# mk3-schield.net
KiCad netlist of a schematic drawn in EAGLE
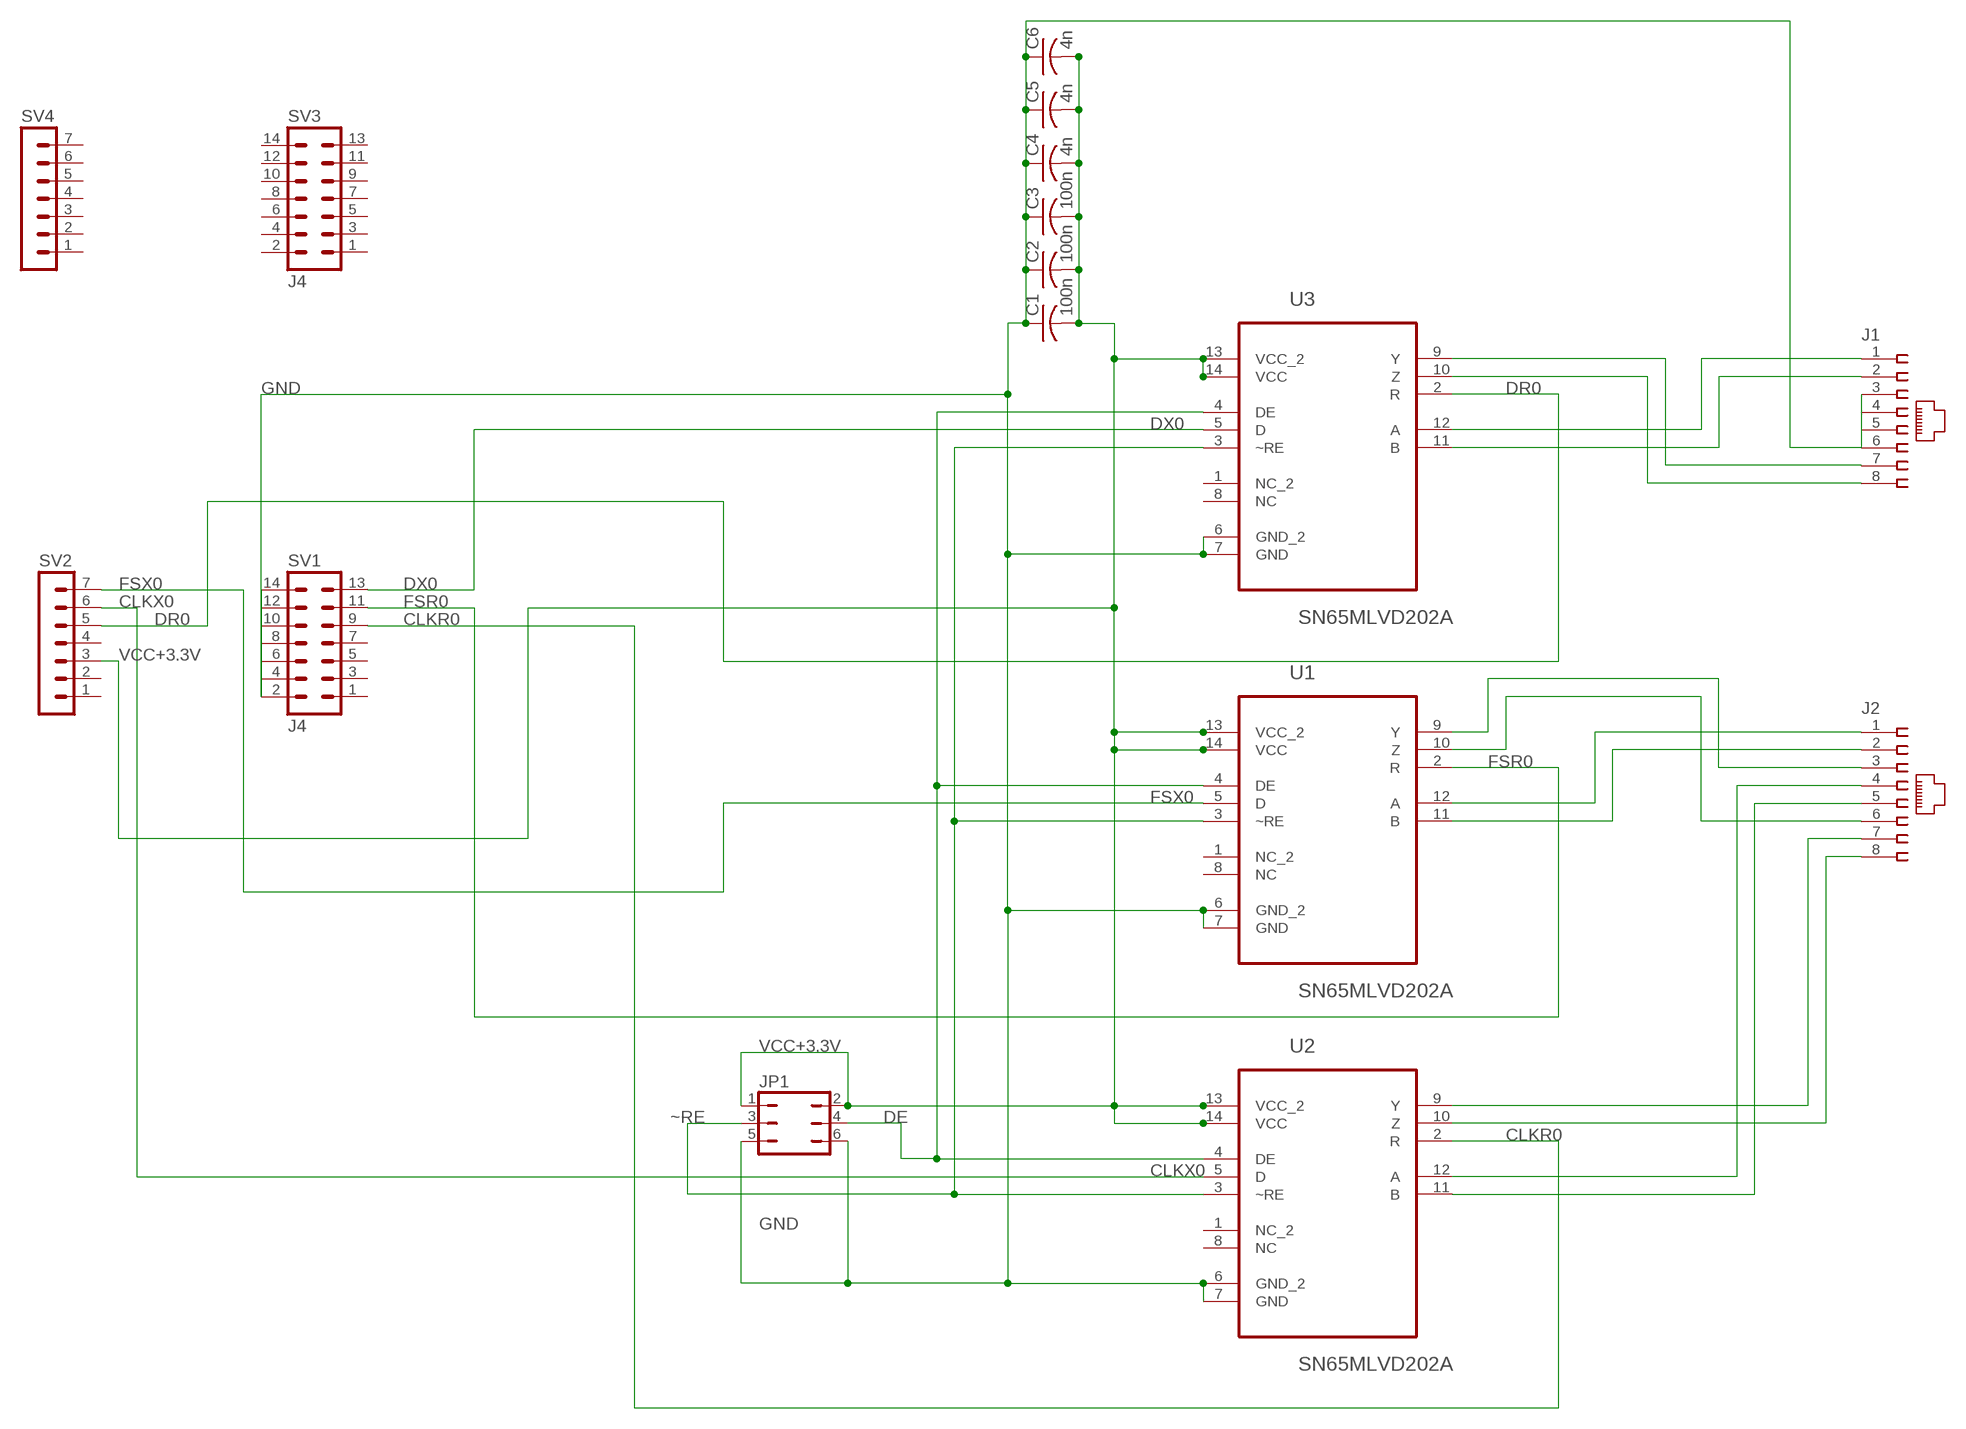
[diagram p0: schematic, sheet 1]

(export (version "E")
  (design (tool "Eeschema 10.0.6"))
  (components
    (comp (ref "C1")
      (value "100n")
      (footprint "eagle-import:C0805")
      (libsource (lib "eagle-import") (part "C-USC0805"))
    )
    (comp (ref "C2")
      (value "100n")
      (footprint "eagle-import:C0805")
      (libsource (lib "eagle-import") (part "C-USC0805"))
    )
    (comp (ref "C3")
      (value "100n")
      (footprint "eagle-import:C0805")
      (libsource (lib "eagle-import") (part "C-USC0805"))
    )
    (comp (ref "C4")
      (value "4n")
      (footprint "eagle-import:C0805")
      (libsource (lib "eagle-import") (part "C-USC0805"))
    )
    (comp (ref "C5")
      (value "4n")
      (footprint "eagle-import:C0805")
      (libsource (lib "eagle-import") (part "C-USC0805"))
    )
    (comp (ref "C6")
      (value "4n")
      (footprint "eagle-import:C0805")
      (libsource (lib "eagle-import") (part "C-USC0805"))
    )
    (comp (ref "J1")
      (value "557785-1-SHIELD")
      (footprint "eagle-import:557785-1")
      (libsource (lib "eagle-import") (part "557785-1-SHIELD"))
    )
    (comp (ref "J2")
      (value "557785-1-SHIELD")
      (footprint "eagle-import:557785-1")
      (libsource (lib "eagle-import") (part "557785-1-SHIELD"))
    )
    (comp (ref "JP1")
      (value "JP3Q")
      (footprint "eagle-import:JP3Q")
      (libsource (lib "eagle-import") (part "JP3Q"))
    )
    (comp (ref "SV1")
      (value "J4")
      (footprint "eagle-import:MA07-2")
      (libsource (lib "eagle-import") (part "MA07-2"))
    )
    (comp (ref "SV2")
      (value "MA07-1")
      (footprint "eagle-import:MA07-1")
      (libsource (lib "eagle-import") (part "MA07-1"))
    )
    (comp (ref "SV3")
      (value "J4")
      (footprint "eagle-import:MA07-2")
      (libsource (lib "eagle-import") (part "MA07-2"))
    )
    (comp (ref "SV4")
      (value "MA07-1")
      (footprint "eagle-import:MA07-1")
      (libsource (lib "eagle-import") (part "MA07-1"))
    )
    (comp (ref "U1")
      (value "SN65MLVD202A")
      (footprint "eagle-import:SOIC127P600X175-14N")
      (fields (field (name "MPN") "SN65MLVD205AD"))
      (libsource (lib "eagle-import") (part "SN65MLVD205AD"))
    )
    (comp (ref "U2")
      (value "SN65MLVD202A")
      (footprint "eagle-import:SOIC127P600X175-14N")
      (fields (field (name "MPN") "SN65MLVD205AD"))
      (libsource (lib "eagle-import") (part "SN65MLVD205AD"))
    )
    (comp (ref "U3")
      (value "SN65MLVD202A")
      (footprint "eagle-import:SOIC127P600X175-14N")
      (fields (field (name "MPN") "SN65MLVD205AD"))
      (libsource (lib "eagle-import") (part "SN65MLVD205AD"))
    )
  )
  (nets
    (net (code "1") (name "/CLKR0") (class "Default")
      (node (ref "SV1") (pin "9") (pinfunction "9_9") (pintype "passive"))
      (node (ref "U2") (pin "2") (pinfunction "R_2") (pintype "output"))
    )
    (net (code "2") (name "/CLKX0") (class "Default")
      (node (ref "SV2") (pin "6") (pinfunction "6_6") (pintype "passive"))
      (node (ref "U2") (pin "5") (pinfunction "D_5") (pintype "input"))
    )
    (net (code "3") (name "/DE") (class "Default")
      (node (ref "JP1") (pin "4") (pinfunction "4_4") (pintype "passive"))
      (node (ref "U1") (pin "4") (pinfunction "DE_4") (pintype "input"))
      (node (ref "U2") (pin "4") (pinfunction "DE_4") (pintype "input"))
      (node (ref "U3") (pin "4") (pinfunction "DE_4") (pintype "input"))
    )
    (net (code "4") (name "/DR0") (class "Default")
      (node (ref "SV2") (pin "5") (pinfunction "5_5") (pintype "passive"))
      (node (ref "U3") (pin "2") (pinfunction "R_2") (pintype "output"))
    )
    (net (code "5") (name "/DX0") (class "Default")
      (node (ref "SV1") (pin "13") (pinfunction "13_13") (pintype "passive"))
      (node (ref "U3") (pin "5") (pinfunction "D_5") (pintype "input"))
    )
    (net (code "6") (name "/FSR0") (class "Default")
      (node (ref "SV1") (pin "11") (pinfunction "11_11") (pintype "passive"))
      (node (ref "U1") (pin "2") (pinfunction "R_2") (pintype "output"))
    )
    (net (code "7") (name "/FSX0") (class "Default")
      (node (ref "SV2") (pin "7") (pinfunction "7_7") (pintype "passive"))
      (node (ref "U1") (pin "5") (pinfunction "D_5") (pintype "input"))
    )
    (net (code "8") (name "/GND") (class "Default")
      (node (ref "C1") (pin "1") (pinfunction "1_1") (pintype "passive"))
      (node (ref "C2") (pin "1") (pinfunction "1_1") (pintype "passive"))
      (node (ref "C3") (pin "1") (pinfunction "1_1") (pintype "passive"))
      (node (ref "C4") (pin "1") (pinfunction "1_1") (pintype "passive"))
      (node (ref "C5") (pin "1") (pinfunction "1_1") (pintype "passive"))
      (node (ref "C6") (pin "1") (pinfunction "1_1") (pintype "passive"))
      (node (ref "J1") (pin "3") (pinfunction "3_3") (pintype "passive"))
      (node (ref "J1") (pin "4") (pinfunction "4_4") (pintype "passive"))
      (node (ref "J1") (pin "5") (pinfunction "5_5") (pintype "passive"))
      (node (ref "J1") (pin "6") (pinfunction "6_6") (pintype "passive"))
      (node (ref "JP1") (pin "5") (pinfunction "5_5") (pintype "passive"))
      (node (ref "JP1") (pin "6") (pinfunction "6_6") (pintype "passive"))
      (node (ref "SV1") (pin "10") (pinfunction "10_10") (pintype "passive"))
      (node (ref "SV1") (pin "12") (pinfunction "12_12") (pintype "passive"))
      (node (ref "SV1") (pin "14") (pinfunction "14_14") (pintype "passive"))
      (node (ref "SV1") (pin "2") (pinfunction "2_2") (pintype "passive"))
      (node (ref "SV1") (pin "4") (pinfunction "4_4") (pintype "passive"))
      (node (ref "SV1") (pin "6") (pinfunction "6_6") (pintype "passive"))
      (node (ref "SV1") (pin "8") (pinfunction "8_8") (pintype "passive"))
      (node (ref "U1") (pin "6") (pinfunction "GND_2_6") (pintype "passive"))
      (node (ref "U1") (pin "7") (pinfunction "GND_7") (pintype "passive"))
      (node (ref "U2") (pin "6") (pinfunction "GND_2_6") (pintype "passive"))
      (node (ref "U2") (pin "7") (pinfunction "GND_7") (pintype "passive"))
      (node (ref "U3") (pin "6") (pinfunction "GND_2_6") (pintype "passive"))
      (node (ref "U3") (pin "7") (pinfunction "GND_7") (pintype "passive"))
    )
    (net (code "9") (name "/VCC+3.3V") (class "Default")
      (node (ref "C1") (pin "2") (pinfunction "2_2") (pintype "passive"))
      (node (ref "C2") (pin "2") (pinfunction "2_2") (pintype "passive"))
      (node (ref "C3") (pin "2") (pinfunction "2_2") (pintype "passive"))
      (node (ref "C4") (pin "2") (pinfunction "2_2") (pintype "passive"))
      (node (ref "C5") (pin "2") (pinfunction "2_2") (pintype "passive"))
      (node (ref "C6") (pin "2") (pinfunction "2_2") (pintype "passive"))
      (node (ref "JP1") (pin "1") (pinfunction "1_1") (pintype "passive"))
      (node (ref "JP1") (pin "2") (pinfunction "2_2") (pintype "passive"))
      (node (ref "SV2") (pin "3") (pinfunction "3_3") (pintype "passive"))
      (node (ref "U1") (pin "13") (pinfunction "VCC_2_13") (pintype "power_in"))
      (node (ref "U1") (pin "14") (pinfunction "VCC_14") (pintype "power_in"))
      (node (ref "U2") (pin "13") (pinfunction "VCC_2_13") (pintype "power_in"))
      (node (ref "U2") (pin "14") (pinfunction "VCC_14") (pintype "power_in"))
      (node (ref "U3") (pin "13") (pinfunction "VCC_2_13") (pintype "power_in"))
      (node (ref "U3") (pin "14") (pinfunction "VCC_14") (pintype "power_in"))
    )
    (net (code "10") (name "/~{RE}") (class "Default")
      (node (ref "JP1") (pin "3") (pinfunction "3_3") (pintype "passive"))
      (node (ref "U1") (pin "3") (pinfunction "~{RE}_3") (pintype "input"))
      (node (ref "U2") (pin "3") (pinfunction "~{RE}_3") (pintype "input"))
      (node (ref "U3") (pin "3") (pinfunction "~{RE}_3") (pintype "input"))
    )
    (net (code "11") (name "Net-(U1-A)") (class "Default")
      (node (ref "J2") (pin "1") (pinfunction "1_1") (pintype "passive"))
      (node (ref "U1") (pin "12") (pinfunction "A_12") (pintype "output"))
    )
    (net (code "12") (name "Net-(U1-B)") (class "Default")
      (node (ref "J2") (pin "2") (pinfunction "2_2") (pintype "passive"))
      (node (ref "U1") (pin "11") (pinfunction "B_11") (pintype "output"))
    )
    (net (code "13") (name "Net-(U1-Y)") (class "Default")
      (node (ref "J2") (pin "3") (pinfunction "3_3") (pintype "passive"))
      (node (ref "U1") (pin "9") (pinfunction "Y_9") (pintype "output"))
    )
    (net (code "14") (name "Net-(U1-Z)") (class "Default")
      (node (ref "J2") (pin "6") (pinfunction "6_6") (pintype "passive"))
      (node (ref "U1") (pin "10") (pinfunction "Z_10") (pintype "output"))
    )
    (net (code "15") (name "Net-(U2-A)") (class "Default")
      (node (ref "J2") (pin "4") (pinfunction "4_4") (pintype "passive"))
      (node (ref "U2") (pin "12") (pinfunction "A_12") (pintype "output"))
    )
    (net (code "16") (name "Net-(U2-B)") (class "Default")
      (node (ref "J2") (pin "5") (pinfunction "5_5") (pintype "passive"))
      (node (ref "U2") (pin "11") (pinfunction "B_11") (pintype "output"))
    )
    (net (code "17") (name "Net-(U2-Y)") (class "Default")
      (node (ref "J2") (pin "7") (pinfunction "7_7") (pintype "passive"))
      (node (ref "U2") (pin "9") (pinfunction "Y_9") (pintype "output"))
    )
    (net (code "18") (name "Net-(U2-Z)") (class "Default")
      (node (ref "J2") (pin "8") (pinfunction "8_8") (pintype "passive"))
      (node (ref "U2") (pin "10") (pinfunction "Z_10") (pintype "output"))
    )
    (net (code "19") (name "Net-(U3-A)") (class "Default")
      (node (ref "J1") (pin "1") (pinfunction "1_1") (pintype "passive"))
      (node (ref "U3") (pin "12") (pinfunction "A_12") (pintype "output"))
    )
    (net (code "20") (name "Net-(U3-B)") (class "Default")
      (node (ref "J1") (pin "2") (pinfunction "2_2") (pintype "passive"))
      (node (ref "U3") (pin "11") (pinfunction "B_11") (pintype "output"))
    )
    (net (code "21") (name "Net-(U3-Y)") (class "Default")
      (node (ref "J1") (pin "7") (pinfunction "7_7") (pintype "passive"))
      (node (ref "U3") (pin "9") (pinfunction "Y_9") (pintype "output"))
    )
    (net (code "22") (name "Net-(U3-Z)") (class "Default")
      (node (ref "J1") (pin "8") (pinfunction "8_8") (pintype "passive"))
      (node (ref "U3") (pin "10") (pinfunction "Z_10") (pintype "output"))
    )
    (net (code "23") (name "unconnected-(SV1-Pad1)") (class "Default")
      (node (ref "SV1") (pin "1") (pinfunction "1_1") (pintype "passive"))
    )
    (net (code "24") (name "unconnected-(SV1-Pad3)") (class "Default")
      (node (ref "SV1") (pin "3") (pinfunction "3_3") (pintype "passive"))
    )
    (net (code "25") (name "unconnected-(SV1-Pad5)") (class "Default")
      (node (ref "SV1") (pin "5") (pinfunction "5_5") (pintype "passive"))
    )
    (net (code "26") (name "unconnected-(SV1-Pad7)") (class "Default")
      (node (ref "SV1") (pin "7") (pinfunction "7_7") (pintype "passive"))
    )
    (net (code "27") (name "unconnected-(SV2-Pad1)") (class "Default")
      (node (ref "SV2") (pin "1") (pinfunction "1_1") (pintype "passive"))
    )
    (net (code "28") (name "unconnected-(SV2-Pad2)") (class "Default")
      (node (ref "SV2") (pin "2") (pinfunction "2_2") (pintype "passive"))
    )
    (net (code "29") (name "unconnected-(SV2-Pad4)") (class "Default")
      (node (ref "SV2") (pin "4") (pinfunction "4_4") (pintype "passive"))
    )
    (net (code "30") (name "unconnected-(SV3-Pad1)") (class "Default")
      (node (ref "SV3") (pin "1") (pinfunction "1_1") (pintype "passive"))
    )
    (net (code "31") (name "unconnected-(SV3-Pad2)") (class "Default")
      (node (ref "SV3") (pin "2") (pinfunction "2_2") (pintype "passive"))
    )
    (net (code "32") (name "unconnected-(SV3-Pad3)") (class "Default")
      (node (ref "SV3") (pin "3") (pinfunction "3_3") (pintype "passive"))
    )
    (net (code "33") (name "unconnected-(SV3-Pad4)") (class "Default")
      (node (ref "SV3") (pin "4") (pinfunction "4_4") (pintype "passive"))
    )
    (net (code "34") (name "unconnected-(SV3-Pad5)") (class "Default")
      (node (ref "SV3") (pin "5") (pinfunction "5_5") (pintype "passive"))
    )
    (net (code "35") (name "unconnected-(SV3-Pad6)") (class "Default")
      (node (ref "SV3") (pin "6") (pinfunction "6_6") (pintype "passive"))
    )
    (net (code "36") (name "unconnected-(SV3-Pad7)") (class "Default")
      (node (ref "SV3") (pin "7") (pinfunction "7_7") (pintype "passive"))
    )
    (net (code "37") (name "unconnected-(SV3-Pad8)") (class "Default")
      (node (ref "SV3") (pin "8") (pinfunction "8_8") (pintype "passive"))
    )
    (net (code "38") (name "unconnected-(SV3-Pad9)") (class "Default")
      (node (ref "SV3") (pin "9") (pinfunction "9_9") (pintype "passive"))
    )
    (net (code "39") (name "unconnected-(SV3-Pad10)") (class "Default")
      (node (ref "SV3") (pin "10") (pinfunction "10_10") (pintype "passive"))
    )
    (net (code "40") (name "unconnected-(SV3-Pad11)") (class "Default")
      (node (ref "SV3") (pin "11") (pinfunction "11_11") (pintype "passive"))
    )
    (net (code "41") (name "unconnected-(SV3-Pad12)") (class "Default")
      (node (ref "SV3") (pin "12") (pinfunction "12_12") (pintype "passive"))
    )
    (net (code "42") (name "unconnected-(SV3-Pad13)") (class "Default")
      (node (ref "SV3") (pin "13") (pinfunction "13_13") (pintype "passive"))
    )
    (net (code "43") (name "unconnected-(SV3-Pad14)") (class "Default")
      (node (ref "SV3") (pin "14") (pinfunction "14_14") (pintype "passive"))
    )
    (net (code "44") (name "unconnected-(SV4-Pad1)") (class "Default")
      (node (ref "SV4") (pin "1") (pinfunction "1_1") (pintype "passive"))
    )
    (net (code "45") (name "unconnected-(SV4-Pad2)") (class "Default")
      (node (ref "SV4") (pin "2") (pinfunction "2_2") (pintype "passive"))
    )
    (net (code "46") (name "unconnected-(SV4-Pad3)") (class "Default")
      (node (ref "SV4") (pin "3") (pinfunction "3_3") (pintype "passive"))
    )
    (net (code "47") (name "unconnected-(SV4-Pad4)") (class "Default")
      (node (ref "SV4") (pin "4") (pinfunction "4_4") (pintype "passive"))
    )
    (net (code "48") (name "unconnected-(SV4-Pad5)") (class "Default")
      (node (ref "SV4") (pin "5") (pinfunction "5_5") (pintype "passive"))
    )
    (net (code "49") (name "unconnected-(SV4-Pad6)") (class "Default")
      (node (ref "SV4") (pin "6") (pinfunction "6_6") (pintype "passive"))
    )
    (net (code "50") (name "unconnected-(SV4-Pad7)") (class "Default")
      (node (ref "SV4") (pin "7") (pinfunction "7_7") (pintype "passive"))
    )
    (net (code "51") (name "unconnected-(U1-NC-Pad8)") (class "Default")
      (node (ref "U1") (pin "8") (pinfunction "NC_8") (pintype "no_connect"))
    )
    (net (code "52") (name "unconnected-(U1-NC_2-Pad1)") (class "Default")
      (node (ref "U1") (pin "1") (pinfunction "NC_2_1") (pintype "no_connect"))
    )
    (net (code "53") (name "unconnected-(U2-NC-Pad8)") (class "Default")
      (node (ref "U2") (pin "8") (pinfunction "NC_8") (pintype "no_connect"))
    )
    (net (code "54") (name "unconnected-(U2-NC_2-Pad1)") (class "Default")
      (node (ref "U2") (pin "1") (pinfunction "NC_2_1") (pintype "no_connect"))
    )
    (net (code "55") (name "unconnected-(U3-NC-Pad8)") (class "Default")
      (node (ref "U3") (pin "8") (pinfunction "NC_8") (pintype "no_connect"))
    )
    (net (code "56") (name "unconnected-(U3-NC_2-Pad1)") (class "Default")
      (node (ref "U3") (pin "1") (pinfunction "NC_2_1") (pintype "no_connect"))
    )
  )
)
